# ZATINO_V2.net
KiCad netlist of a schematic drawn in EAGLE
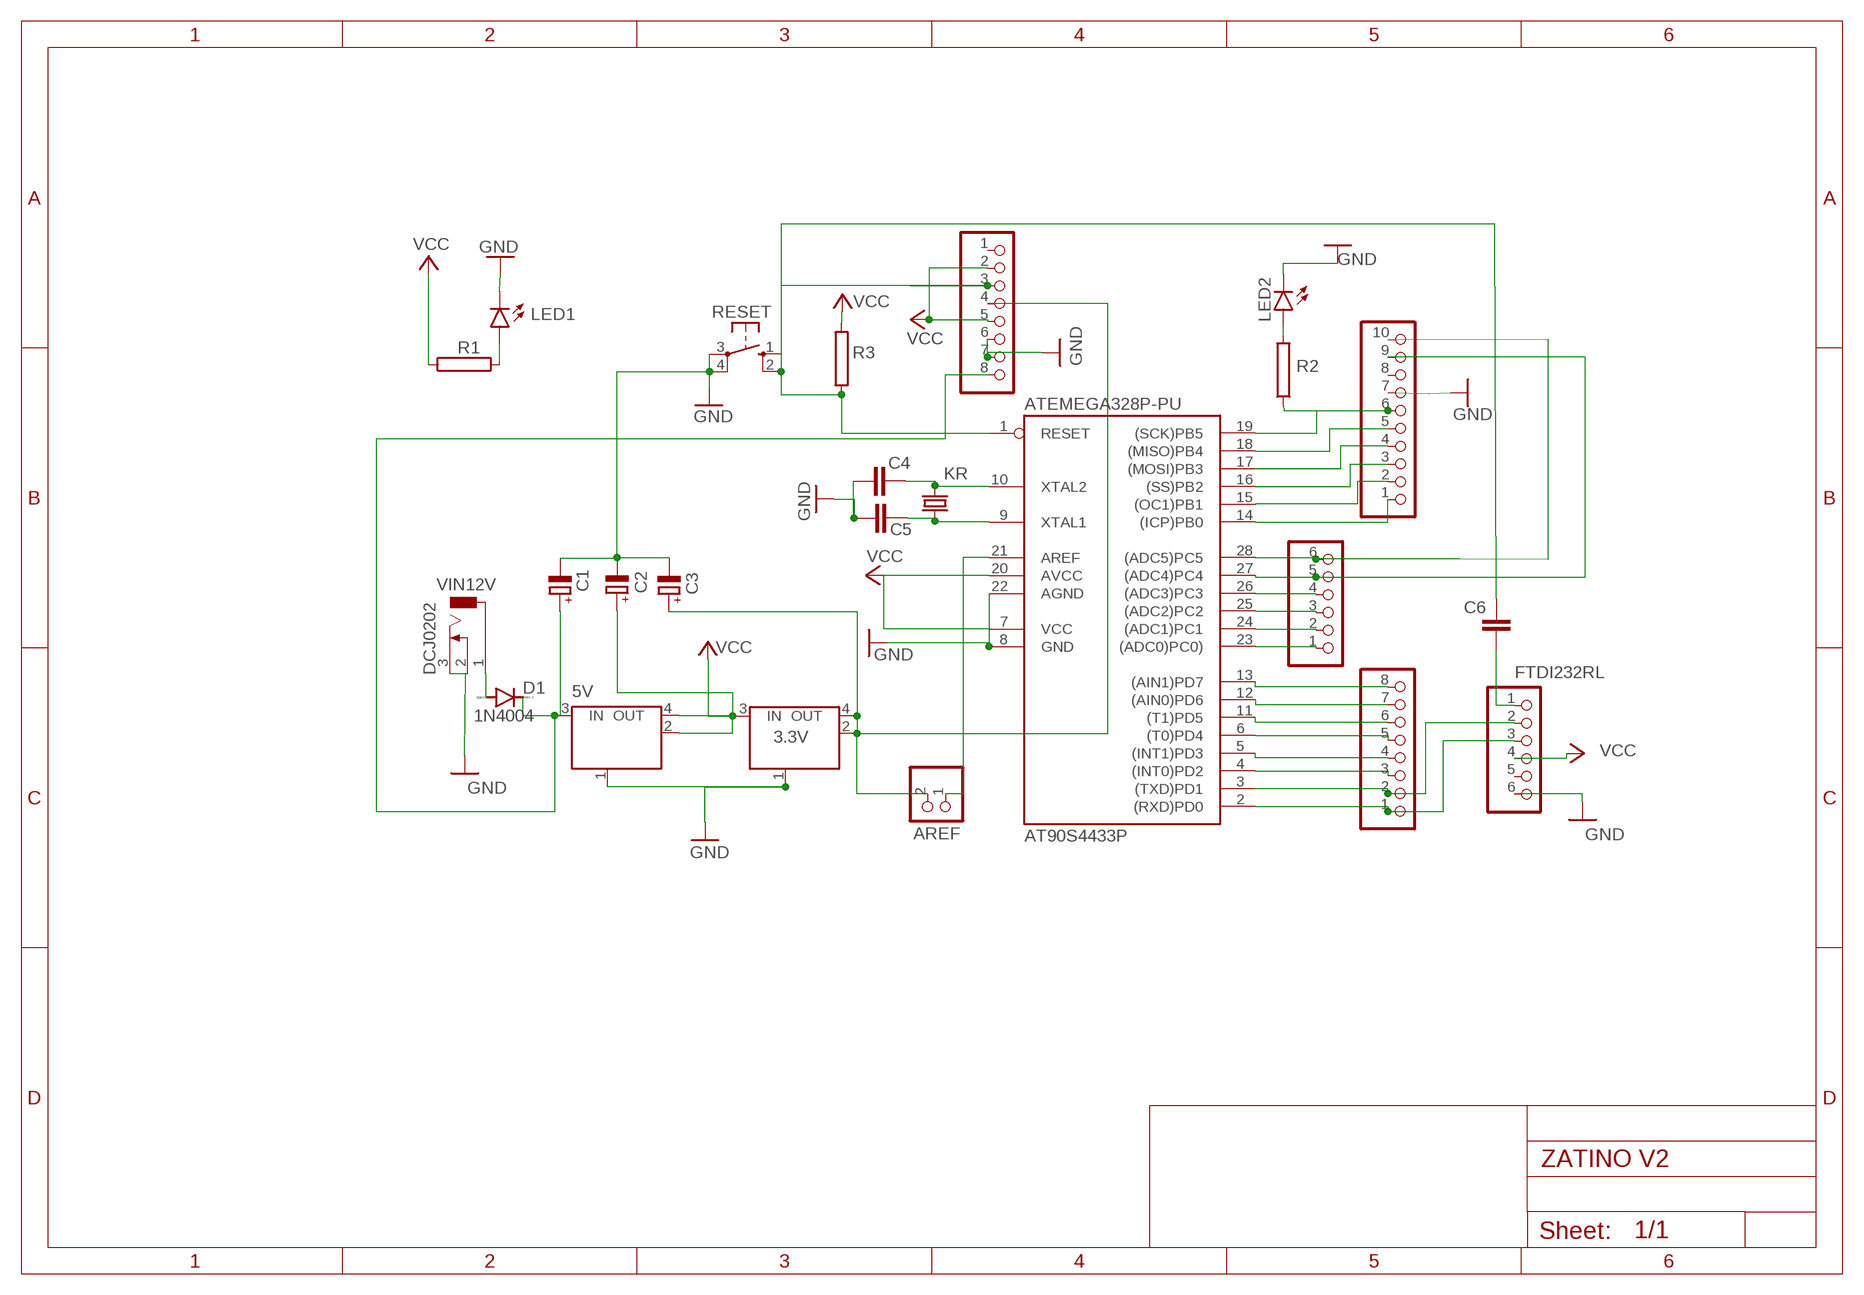
[diagram p0: schematic, sheet 1]

(export (version "E")
  (design (tool "Eeschema 10.0.6"))
  (components
    (comp (ref "3.3V")
      (value "MC33269ST-3.3T3")
      (footprint "eagle-import:SOT223")
      (libsource (lib "eagle-import") (part "MC33269ST-3.3T3"))
    )
    (comp (ref "5V")
      (value "MC33269ST-3.3T3")
      (footprint "eagle-import:SOT223")
      (libsource (lib "eagle-import") (part "MC33269ST-3.3T3"))
    )
    (comp (ref "AD")
      (value "6x1F-H8.5")
      (footprint "eagle-import:1X06")
      (libsource (lib "eagle-import") (part "PINHD-1X6"))
    )
    (comp (ref "ATEMEGA328P-PU")
      (value "AT90S4433P")
      (footprint "eagle-import:DIL28-3")
      (libsource (lib "eagle-import") (part "AT90S4433P"))
    )
    (comp (ref "C1")
      (value "CPOL-EUE2,5-6E")
      (footprint "eagle-import:E2,5-6E")
      (libsource (lib "eagle-import") (part "CPOL-EUE2,5-6E"))
    )
    (comp (ref "C2")
      (value "CPOL-EUE2,5-6E")
      (footprint "eagle-import:E2,5-6E")
      (libsource (lib "eagle-import") (part "CPOL-EUE2,5-6E"))
    )
    (comp (ref "C3")
      (value "CPOL-EUE2,5-6E")
      (footprint "eagle-import:E2,5-6E")
      (libsource (lib "eagle-import") (part "CPOL-EUE2,5-6E"))
    )
    (comp (ref "C4")
      (value "C2.5/2")
      (footprint "eagle-import:C2.5-2")
      (libsource (lib "eagle-import") (part "C2.5/2"))
    )
    (comp (ref "C5")
      (value "C2.5/2")
      (footprint "eagle-import:C2.5-2")
      (libsource (lib "eagle-import") (part "C2.5/2"))
    )
    (comp (ref "C6")
      (value "C2,5-3")
      (footprint "eagle-import:C2.5-3")
      (libsource (lib "eagle-import") (part "C2,5-3"))
    )
    (comp (ref "D1")
      (value "1N4004")
      (footprint "eagle-import:DO41-10")
      (libsource (lib "eagle-import") (part "1N4004"))
    )
    (comp (ref "FTDI232RL")
      (value "PINHD-1X6")
      (footprint "eagle-import:1X06")
      (libsource (lib "eagle-import") (part "pinhead_325_PINHD-1X6"))
    )
    (comp (ref "IOH")
      (value "10x1F-H8.5")
      (footprint "eagle-import:1X10")
      (libsource (lib "eagle-import") (part "PINHD-1X10_ARD"))
    )
    (comp (ref "IOL")
      (value "8x1F-H8.5")
      (footprint "eagle-import:1X08")
      (libsource (lib "eagle-import") (part "PINHD-1X8"))
    )
    (comp (ref "JP2")
      (value "PINHD-1X2")
      (footprint "eagle-import:1X02")
      (libsource (lib "eagle-import") (part "PINHD-1X2"))
    )
    (comp (ref "KR")
      (value "CRYSTALHC49U-V")
      (footprint "eagle-import:HC49U-V")
      (libsource (lib "eagle-import") (part "CRYSTALHC49U-V"))
    )
    (comp (ref "LED1")
      (value "LED5MM")
      (footprint "eagle-import:LED5MM")
      (libsource (lib "eagle-import") (part "LED5MM"))
    )
    (comp (ref "LED2")
      (value "LED5MM")
      (footprint "eagle-import:LED5MM")
      (libsource (lib "eagle-import") (part "LED5MM"))
    )
    (comp (ref "POWER")
      (value "8x1F-H8.5")
      (footprint "eagle-import:1X08")
      (libsource (lib "eagle-import") (part "PINHD-1X8"))
    )
    (comp (ref "R1")
      (value "RRS1/8")
      (footprint "eagle-import:RS1_8")
      (libsource (lib "eagle-import") (part "RRS1/8"))
    )
    (comp (ref "R2")
      (value "RRS1/8")
      (footprint "eagle-import:RS1_8")
      (libsource (lib "eagle-import") (part "RRS1/8"))
    )
    (comp (ref "R3")
      (value "RRS1/4")
      (footprint "eagle-import:RS1_4")
      (fields (field (name "MF") "OHMITE") (field (name "MPN") "RRS1K0"))
      (libsource (lib "eagle-import") (part "RRS1/4"))
    )
    (comp (ref "RESET")
      (value "10-XX")
      (footprint "eagle-import:B3F-10XX")
      (fields (field (name "MPN") "B3F-1000"))
      (libsource (lib "eagle-import") (part "10-XX"))
    )
    (comp (ref "VIN12V")
      (value "DCJ0202")
      (footprint "eagle-import:DCJ0202")
      (libsource (lib "eagle-import") (part "DCJ0202"))
    )
  )
  (nets
    (net (code "1") (name "GND") (class "Default")
      (node (ref "3.3V") (pin "1") (pinfunction "GND/ADJ_1") (pintype "input"))
      (node (ref "5V") (pin "1") (pinfunction "GND/ADJ_1") (pintype "input"))
      (node (ref "ATEMEGA328P-PU") (pin "22") (pinfunction "AGND_22") (pintype "power_in"))
      (node (ref "ATEMEGA328P-PU") (pin "8") (pinfunction "GND_8") (pintype "power_in"))
      (node (ref "C1") (pin "-") (pinfunction "-_-") (pintype "passive"))
      (node (ref "C2") (pin "-") (pinfunction "-_-") (pintype "passive"))
      (node (ref "C3") (pin "-") (pinfunction "-_-") (pintype "passive"))
      (node (ref "C4") (pin "1") (pinfunction "1_1") (pintype "passive"))
      (node (ref "C5") (pin "1") (pinfunction "1_1") (pintype "passive"))
      (node (ref "FTDI232RL") (pin "6") (pinfunction "6_6") (pintype "passive"))
      (node (ref "IOH") (pin "7") (pinfunction "7_7") (pintype "passive"))
      (node (ref "LED1") (pin "K") (pinfunction "C_K") (pintype "passive"))
      (node (ref "LED2") (pin "K") (pinfunction "C_K") (pintype "passive"))
      (node (ref "POWER") (pin "6") (pinfunction "6_6") (pintype "passive"))
      (node (ref "POWER") (pin "7") (pinfunction "7_7") (pintype "passive"))
      (node (ref "RESET") (pin "3") (pinfunction "P_3") (pintype "passive"))
      (node (ref "RESET") (pin "4") (pinfunction "P1_4") (pintype "passive"))
      (node (ref "VIN12V") (pin "2") (pinfunction "2_2") (pintype "passive"))
      (node (ref "VIN12V") (pin "3") (pinfunction "3_3") (pintype "passive"))
    )
    (net (code "2") (name "Net-(3.3V-OUT-Pad2)") (class "Default")
      (node (ref "3.3V") (pin "2") (pinfunction "OUT_2") (pintype "passive"))
      (node (ref "3.3V") (pin "4") (pinfunction "OUT_4") (pintype "passive"))
      (node (ref "C3") (pin "+") (pinfunction "+_+") (pintype "passive"))
      (node (ref "JP2") (pin "2") (pinfunction "2_2") (pintype "passive"))
      (node (ref "POWER") (pin "4") (pinfunction "4_4") (pintype "passive"))
    )
    (net (code "3") (name "Net-(5V-IN)") (class "Default")
      (node (ref "5V") (pin "3") (pinfunction "IN_3") (pintype "input"))
      (node (ref "C1") (pin "+") (pinfunction "+_+") (pintype "passive"))
      (node (ref "D1") (pin "C") (pinfunction "C_C") (pintype "passive"))
      (node (ref "POWER") (pin "8") (pinfunction "8_8") (pintype "passive"))
    )
    (net (code "4") (name "Net-(ATEMEGA328P-PU-(ADC0)PC0))") (class "Default")
      (node (ref "AD") (pin "1") (pinfunction "1_1") (pintype "passive"))
      (node (ref "ATEMEGA328P-PU") (pin "23") (pinfunction "(ADC0)PC0)_23") (pintype "bidirectional"))
    )
    (net (code "5") (name "Net-(ATEMEGA328P-PU-(ADC1)PC1)") (class "Default")
      (node (ref "AD") (pin "2") (pinfunction "2_2") (pintype "passive"))
      (node (ref "ATEMEGA328P-PU") (pin "24") (pinfunction "(ADC1)PC1_24") (pintype "bidirectional"))
    )
    (net (code "6") (name "Net-(ATEMEGA328P-PU-(ADC2)PC2)") (class "Default")
      (node (ref "AD") (pin "3") (pinfunction "3_3") (pintype "passive"))
      (node (ref "ATEMEGA328P-PU") (pin "25") (pinfunction "(ADC2)PC2_25") (pintype "bidirectional"))
    )
    (net (code "7") (name "Net-(ATEMEGA328P-PU-(ADC3)PC3)") (class "Default")
      (node (ref "AD") (pin "4") (pinfunction "4_4") (pintype "passive"))
      (node (ref "ATEMEGA328P-PU") (pin "26") (pinfunction "(ADC3)PC3_26") (pintype "bidirectional"))
    )
    (net (code "8") (name "Net-(ATEMEGA328P-PU-(ADC4)PC4)") (class "Default")
      (node (ref "AD") (pin "5") (pinfunction "5_5") (pintype "passive"))
      (node (ref "ATEMEGA328P-PU") (pin "27") (pinfunction "(ADC4)PC4_27") (pintype "bidirectional"))
      (node (ref "IOH") (pin "9") (pinfunction "9_9") (pintype "passive"))
    )
    (net (code "9") (name "Net-(ATEMEGA328P-PU-(ADC5)PC5)") (class "Default")
      (node (ref "AD") (pin "6") (pinfunction "6_6") (pintype "passive"))
      (node (ref "ATEMEGA328P-PU") (pin "28") (pinfunction "(ADC5)PC5_28") (pintype "bidirectional"))
      (node (ref "IOH") (pin "10") (pinfunction "10_10") (pintype "passive"))
    )
    (net (code "10") (name "Net-(ATEMEGA328P-PU-(AIN0)PD6)") (class "Default")
      (node (ref "ATEMEGA328P-PU") (pin "12") (pinfunction "(AIN0)PD6_12") (pintype "bidirectional"))
      (node (ref "IOL") (pin "7") (pinfunction "7_7") (pintype "passive"))
    )
    (net (code "11") (name "Net-(ATEMEGA328P-PU-(AIN1)PD7)") (class "Default")
      (node (ref "ATEMEGA328P-PU") (pin "13") (pinfunction "(AIN1)PD7_13") (pintype "bidirectional"))
      (node (ref "IOL") (pin "8") (pinfunction "8_8") (pintype "passive"))
    )
    (net (code "12") (name "Net-(ATEMEGA328P-PU-(ICP)PB0)") (class "Default")
      (node (ref "ATEMEGA328P-PU") (pin "14") (pinfunction "(ICP)PB0_14") (pintype "bidirectional"))
      (node (ref "IOH") (pin "1") (pinfunction "1_1") (pintype "passive"))
    )
    (net (code "13") (name "Net-(ATEMEGA328P-PU-(INT0)PD2)") (class "Default")
      (node (ref "ATEMEGA328P-PU") (pin "4") (pinfunction "(INT0)PD2_4") (pintype "bidirectional"))
      (node (ref "IOL") (pin "3") (pinfunction "3_3") (pintype "passive"))
    )
    (net (code "14") (name "Net-(ATEMEGA328P-PU-(INT1)PD3)") (class "Default")
      (node (ref "ATEMEGA328P-PU") (pin "5") (pinfunction "(INT1)PD3_5") (pintype "bidirectional"))
      (node (ref "IOL") (pin "4") (pinfunction "4_4") (pintype "passive"))
    )
    (net (code "15") (name "Net-(ATEMEGA328P-PU-(MISO)PB4)") (class "Default")
      (node (ref "ATEMEGA328P-PU") (pin "18") (pinfunction "(MISO)PB4_18") (pintype "bidirectional"))
      (node (ref "IOH") (pin "5") (pinfunction "5_5") (pintype "passive"))
    )
    (net (code "16") (name "Net-(ATEMEGA328P-PU-(MOSI)PB3)") (class "Default")
      (node (ref "ATEMEGA328P-PU") (pin "17") (pinfunction "(MOSI)PB3_17") (pintype "bidirectional"))
      (node (ref "IOH") (pin "4") (pinfunction "4_4") (pintype "passive"))
    )
    (net (code "17") (name "Net-(ATEMEGA328P-PU-(OC1)PB1)") (class "Default")
      (node (ref "ATEMEGA328P-PU") (pin "15") (pinfunction "(OC1)PB1_15") (pintype "bidirectional"))
      (node (ref "IOH") (pin "2") (pinfunction "2_2") (pintype "passive"))
    )
    (net (code "18") (name "Net-(ATEMEGA328P-PU-(RXD)PD0)") (class "Default")
      (node (ref "ATEMEGA328P-PU") (pin "2") (pinfunction "(RXD)PD0_2") (pintype "bidirectional"))
      (node (ref "FTDI232RL") (pin "3") (pinfunction "3_3") (pintype "passive"))
      (node (ref "IOL") (pin "1") (pinfunction "1_1") (pintype "passive"))
    )
    (net (code "19") (name "Net-(ATEMEGA328P-PU-(SCK)PB5)") (class "Default")
      (node (ref "ATEMEGA328P-PU") (pin "19") (pinfunction "(SCK)PB5_19") (pintype "bidirectional"))
      (node (ref "IOH") (pin "6") (pinfunction "6_6") (pintype "passive"))
      (node (ref "R2") (pin "1") (pinfunction "1_1") (pintype "passive"))
    )
    (net (code "20") (name "Net-(ATEMEGA328P-PU-(SS)PB2)") (class "Default")
      (node (ref "ATEMEGA328P-PU") (pin "16") (pinfunction "(SS)PB2_16") (pintype "bidirectional"))
      (node (ref "IOH") (pin "3") (pinfunction "3_3") (pintype "passive"))
    )
    (net (code "21") (name "Net-(ATEMEGA328P-PU-(T0)PD4)") (class "Default")
      (node (ref "ATEMEGA328P-PU") (pin "6") (pinfunction "(T0)PD4_6") (pintype "bidirectional"))
      (node (ref "IOL") (pin "5") (pinfunction "5_5") (pintype "passive"))
    )
    (net (code "22") (name "Net-(ATEMEGA328P-PU-(T1)PD5)") (class "Default")
      (node (ref "ATEMEGA328P-PU") (pin "11") (pinfunction "(T1)PD5_11") (pintype "bidirectional"))
      (node (ref "IOL") (pin "6") (pinfunction "6_6") (pintype "passive"))
    )
    (net (code "23") (name "Net-(ATEMEGA328P-PU-(TXD)PD1)") (class "Default")
      (node (ref "ATEMEGA328P-PU") (pin "3") (pinfunction "(TXD)PD1_3") (pintype "bidirectional"))
      (node (ref "FTDI232RL") (pin "2") (pinfunction "2_2") (pintype "passive"))
      (node (ref "IOL") (pin "2") (pinfunction "2_2") (pintype "passive"))
    )
    (net (code "24") (name "Net-(ATEMEGA328P-PU-AREF)") (class "Default")
      (node (ref "ATEMEGA328P-PU") (pin "21") (pinfunction "AREF_21") (pintype "passive"))
      (node (ref "JP2") (pin "1") (pinfunction "1_1") (pintype "passive"))
    )
    (net (code "25") (name "Net-(ATEMEGA328P-PU-RESET)") (class "Default")
      (node (ref "ATEMEGA328P-PU") (pin "1") (pinfunction "RESET_1") (pintype "input"))
      (node (ref "C6") (pin "2") (pinfunction "2_2") (pintype "passive"))
      (node (ref "POWER") (pin "3") (pinfunction "3_3") (pintype "passive"))
      (node (ref "R3") (pin "1") (pinfunction "1_1") (pintype "passive"))
      (node (ref "RESET") (pin "1") (pinfunction "S_1") (pintype "passive"))
      (node (ref "RESET") (pin "2") (pinfunction "S1_2") (pintype "passive"))
    )
    (net (code "26") (name "Net-(ATEMEGA328P-PU-XTAL1)") (class "Default")
      (node (ref "ATEMEGA328P-PU") (pin "9") (pinfunction "XTAL1_9") (pintype "bidirectional"))
      (node (ref "C5") (pin "2") (pinfunction "2_2") (pintype "passive"))
      (node (ref "KR") (pin "1") (pinfunction "1_1") (pintype "passive"))
    )
    (net (code "27") (name "Net-(ATEMEGA328P-PU-XTAL2)") (class "Default")
      (node (ref "ATEMEGA328P-PU") (pin "10") (pinfunction "XTAL2_10") (pintype "bidirectional"))
      (node (ref "C4") (pin "2") (pinfunction "2_2") (pintype "passive"))
      (node (ref "KR") (pin "2") (pinfunction "2_2") (pintype "passive"))
    )
    (net (code "28") (name "Net-(C6-Pad1)") (class "Default")
      (node (ref "C6") (pin "1") (pinfunction "1_1") (pintype "passive"))
      (node (ref "FTDI232RL") (pin "1") (pinfunction "1_1") (pintype "passive"))
    )
    (net (code "29") (name "Net-(D1-PadA)") (class "Default")
      (node (ref "D1") (pin "A") (pinfunction "A_A") (pintype "passive"))
      (node (ref "VIN12V") (pin "1") (pinfunction "1_1") (pintype "passive"))
    )
    (net (code "30") (name "Net-(LED1-PadA)") (class "Default")
      (node (ref "LED1") (pin "A") (pinfunction "A_A") (pintype "passive"))
      (node (ref "R1") (pin "2") (pinfunction "2_2") (pintype "passive"))
    )
    (net (code "31") (name "Net-(LED2-PadA)") (class "Default")
      (node (ref "LED2") (pin "A") (pinfunction "A_A") (pintype "passive"))
      (node (ref "R2") (pin "2") (pinfunction "2_2") (pintype "passive"))
    )
    (net (code "32") (name "VCC") (class "Default")
      (node (ref "3.3V") (pin "3") (pinfunction "IN_3") (pintype "input"))
      (node (ref "5V") (pin "2") (pinfunction "OUT_2") (pintype "passive"))
      (node (ref "5V") (pin "4") (pinfunction "OUT_4") (pintype "passive"))
      (node (ref "ATEMEGA328P-PU") (pin "20") (pinfunction "AVCC_20") (pintype "power_in"))
      (node (ref "ATEMEGA328P-PU") (pin "7") (pinfunction "VCC_7") (pintype "power_in"))
      (node (ref "C2") (pin "+") (pinfunction "+_+") (pintype "passive"))
      (node (ref "FTDI232RL") (pin "4") (pinfunction "4_4") (pintype "passive"))
      (node (ref "POWER") (pin "2") (pinfunction "2_2") (pintype "passive"))
      (node (ref "POWER") (pin "5") (pinfunction "5_5") (pintype "passive"))
      (node (ref "R1") (pin "1") (pinfunction "1_1") (pintype "passive"))
      (node (ref "R3") (pin "2") (pinfunction "2_2") (pintype "passive"))
    )
    (net (code "33") (name "unconnected-(FTDI232RL-Pad5)") (class "Default")
      (node (ref "FTDI232RL") (pin "5") (pinfunction "5_5") (pintype "passive"))
    )
    (net (code "34") (name "unconnected-(IOH-Pad8)") (class "Default")
      (node (ref "IOH") (pin "8") (pinfunction "8_8") (pintype "passive"))
    )
    (net (code "35") (name "unconnected-(POWER-Pad1)") (class "Default")
      (node (ref "POWER") (pin "1") (pinfunction "1_1") (pintype "passive"))
    )
  )
)
